# GateAndFanControl.net
KiCad netlist of a schematic drawn in Altium Designer
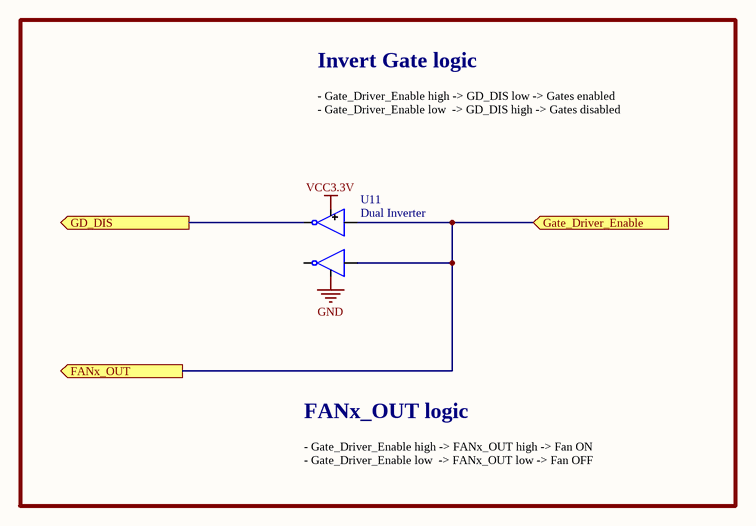
[diagram p0: GateAndFanControl.SchDoc]

(export (version "E")
  (design (tool "Eeschema 10.0.6"))
  (components
    (comp (ref "U11")
      (value "Dual Inverter")
      (footprint "SN74LVC2GU04DCKR")
      (description "This dual inverter is designed for 1.65-V to 5.5-V VCC\r\noperation.")
      (fields (field (name "LCSC PART NUMBER") "C116660"))
      (libsource (lib "UZOhm_Optical") (part "SN74LVC2GU04DCKR"))
    )
  )
  (nets
    (net (code "1") (name "/FANx_OUT") (class "Default")
      (node (ref "U11") (pin "1") (pinfunction "IN1_1") (pintype "passive"))
      (node (ref "U11") (pin "3") (pinfunction "IN2_3") (pintype "passive"))
    )
    (net (code "2") (name "/GD_DIS") (class "Default")
      (node (ref "U11") (pin "6") (pinfunction "OUT2_6") (pintype "passive"))
    )
    (net (code "3") (name "GND") (class "Default")
      (node (ref "U11") (pin "2") (pinfunction "GND_2") (pintype "passive"))
    )
    (net (code "4") (name "VCC3.3V") (class "Default")
      (node (ref "U11") (pin "5") (pinfunction "VCC_5") (pintype "passive"))
    )
    (net (code "5") (name "unconnected-(U11-OUT2-Pad4)") (class "Default")
      (node (ref "U11") (pin "4") (pinfunction "OUT2_4") (pintype "passive"))
    )
  )
)
